# midi2neopixel.net
KiCad netlist of a schematic drawn in EAGLE
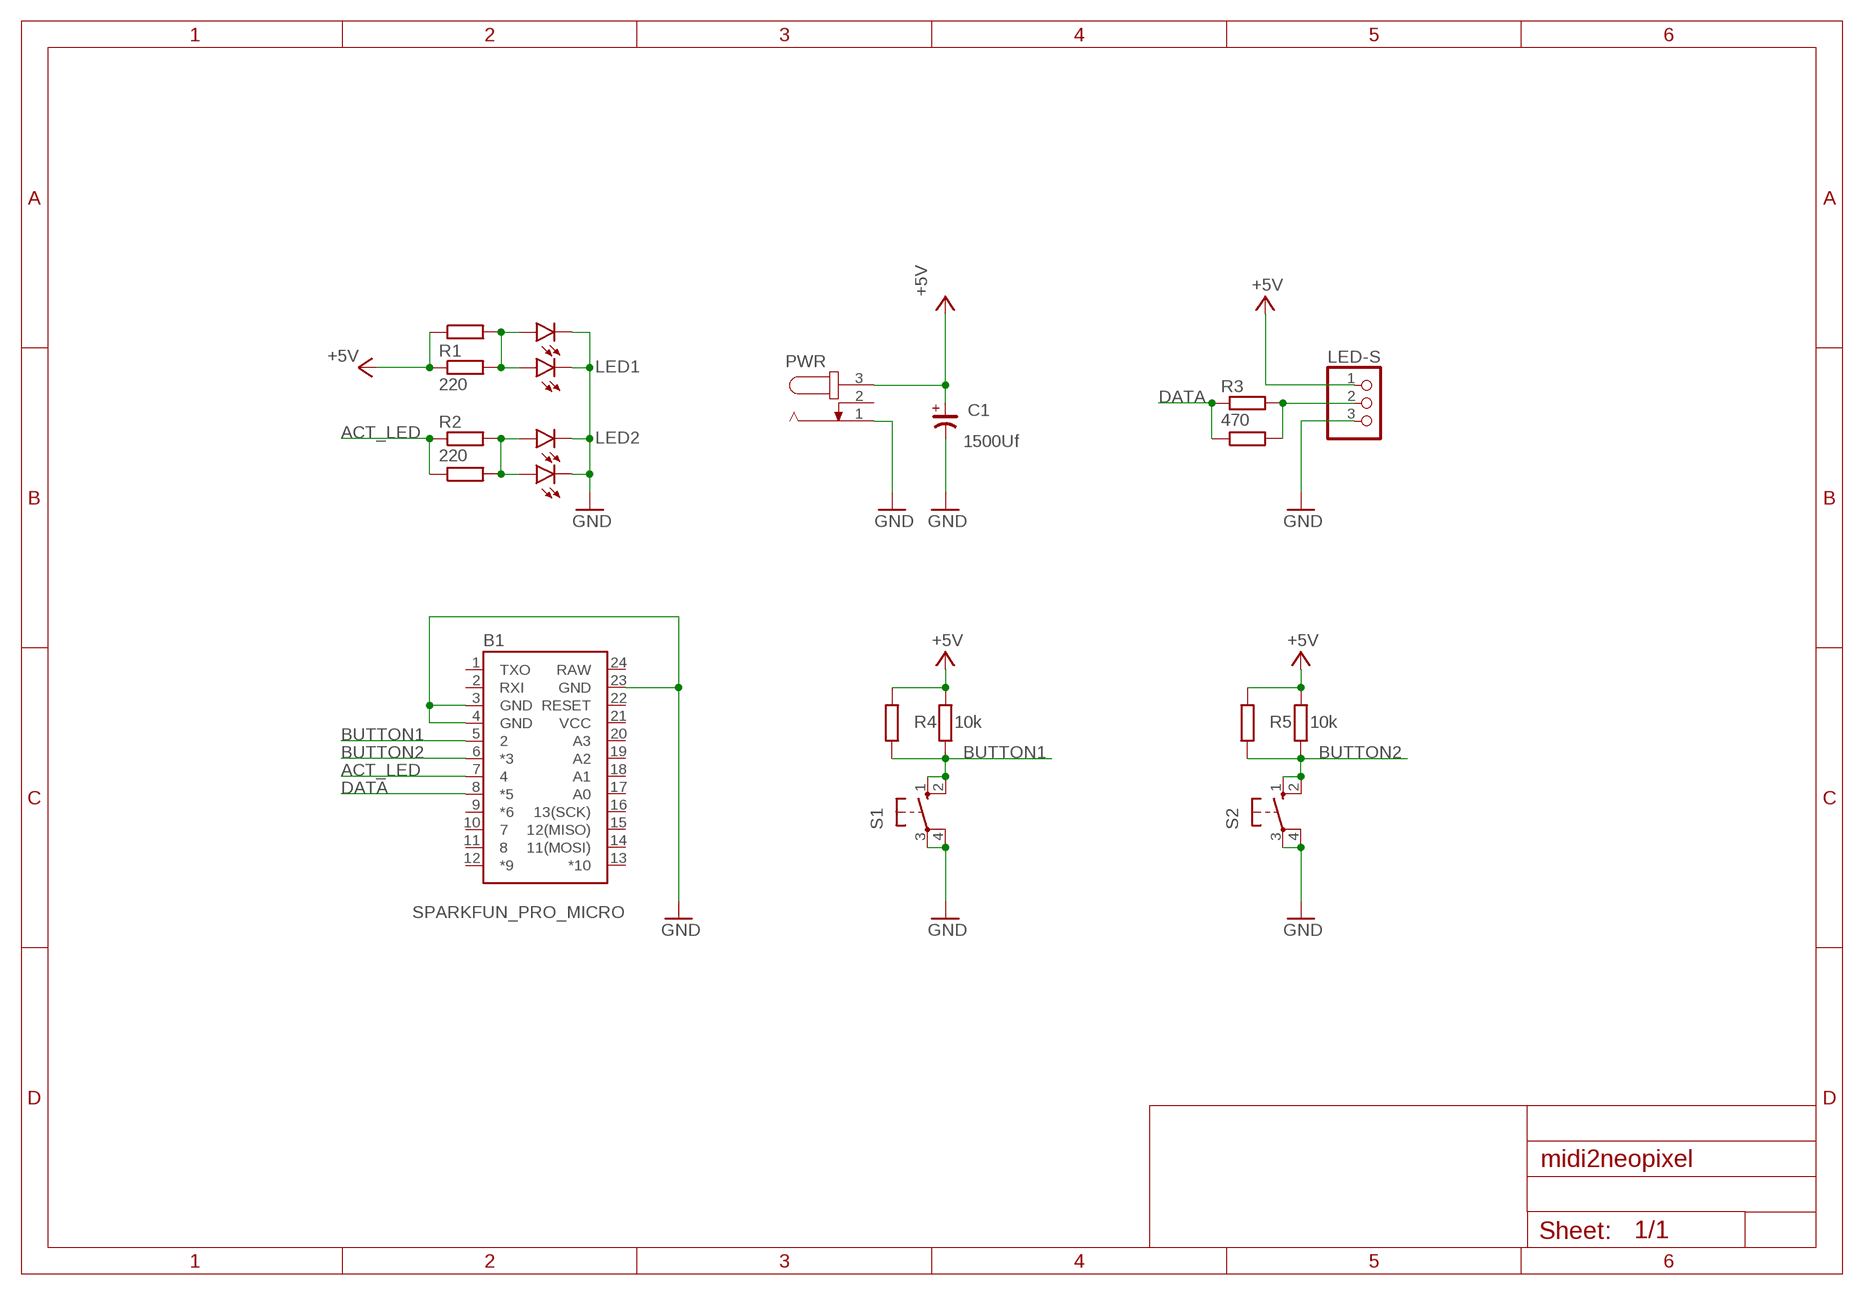
[diagram p0: schematic, sheet 1]

(export (version "E")
  (design (tool "Eeschema 10.0.6"))
  (components
    (comp (ref "B1")
      (value "SPARKFUN_PRO_MICRO")
      (footprint "eagle-import:SPARKFUN_PRO_MICRO")
      (libsource (lib "eagle-import") (part "SPARKFUN_PRO_MICRO"))
    )
    (comp (ref "C1")
      (value "1500Uf")
      (footprint "eagle-import:CEH-050-100X200")
      (libsource (lib "eagle-import") (part "CP_EH-050-100X200"))
    )
    (comp (ref "LED-S")
      (value "PINHD-1X3")
      (footprint "eagle-import:1X03")
      (libsource (lib "eagle-import") (part "PINHD-1X3"))
    )
    (comp (ref "LED1")
      (value "Green")
      (footprint "eagle-import:LED3MM")
      (libsource (lib "eagle-import") (part "LED3MM"))
    )
    (comp (ref "LED2")
      (value "Red")
      (footprint "eagle-import:LED3MM")
      (libsource (lib "eagle-import") (part "LED3MM"))
    )
    (comp (ref "LEDX1")
      (value "LEDSML0603")
      (footprint "eagle-import:SML0603")
      (libsource (lib "eagle-import") (part "LEDSML0603"))
    )
    (comp (ref "LEDX2")
      (value "LEDSML0603")
      (footprint "eagle-import:SML0603")
      (libsource (lib "eagle-import") (part "LEDSML0603"))
    )
    (comp (ref "PWR")
      (value "JACK-PLUG0")
      (footprint "eagle-import:SPC4077")
      (libsource (lib "eagle-import") (part "JACK-PLUG0"))
    )
    (comp (ref "R1")
      (value "220")
      (footprint "eagle-import:0207_7")
      (libsource (lib "eagle-import") (part "R-EU_0207/7"))
    )
    (comp (ref "R2")
      (value "220")
      (footprint "eagle-import:0207_7")
      (libsource (lib "eagle-import") (part "R-EU_0207/7"))
    )
    (comp (ref "R3")
      (value "470")
      (footprint "eagle-import:0207_7")
      (libsource (lib "eagle-import") (part "R-EU_0207/7"))
    )
    (comp (ref "R4")
      (value "10k")
      (footprint "eagle-import:0207_7")
      (libsource (lib "eagle-import") (part "R-EU_0207/7"))
    )
    (comp (ref "R5")
      (value "10k")
      (footprint "eagle-import:0207_7")
      (libsource (lib "eagle-import") (part "R-EU_0207/7"))
    )
    (comp (ref "RR1")
      (value "220")
      (footprint "eagle-import:R0603")
      (libsource (lib "eagle-import") (part "R-EU_R0603"))
    )
    (comp (ref "RR2")
      (value "220")
      (footprint "eagle-import:R0603")
      (libsource (lib "eagle-import") (part "R-EU_R0603"))
    )
    (comp (ref "RR3")
      (value "470")
      (footprint "eagle-import:R0603")
      (libsource (lib "eagle-import") (part "R-EU_R0603"))
    )
    (comp (ref "RR4")
      (value "10k")
      (footprint "eagle-import:R0603")
      (libsource (lib "eagle-import") (part "R-EU_R0603"))
    )
    (comp (ref "RR5")
      (value "10k")
      (footprint "eagle-import:R0603")
      (libsource (lib "eagle-import") (part "R-EU_R0603"))
    )
    (comp (ref "S1")
      (value "10-XX")
      (footprint "eagle-import:B3F-10XX")
      (fields (field (name "MPN") "B3F-1000"))
      (libsource (lib "eagle-import") (part "10-XX"))
    )
    (comp (ref "S2")
      (value "10-XX")
      (footprint "eagle-import:B3F-10XX")
      (fields (field (name "MPN") "B3F-1000"))
      (libsource (lib "eagle-import") (part "10-XX"))
    )
  )
  (nets
    (net (code "1") (name "+5V") (class "Default")
      (node (ref "C1") (pin "+") (pinfunction "+_+") (pintype "passive"))
      (node (ref "LED-S") (pin "1") (pinfunction "1_1") (pintype "passive"))
      (node (ref "PWR") (pin "3") (pinfunction "3_3") (pintype "passive"))
      (node (ref "R1") (pin "1") (pinfunction "1_1") (pintype "passive"))
      (node (ref "R4") (pin "2") (pinfunction "2_2") (pintype "passive"))
      (node (ref "R5") (pin "2") (pinfunction "2_2") (pintype "passive"))
      (node (ref "RR1") (pin "1") (pinfunction "1_1") (pintype "passive"))
      (node (ref "RR4") (pin "2") (pinfunction "2_2") (pintype "passive"))
      (node (ref "RR5") (pin "2") (pinfunction "2_2") (pintype "passive"))
    )
    (net (code "2") (name "/ACT_LED") (class "Default")
      (node (ref "B1") (pin "7") (pinfunction "4_7") (pintype "bidirectional"))
      (node (ref "R2") (pin "1") (pinfunction "1_1") (pintype "passive"))
      (node (ref "RR2") (pin "1") (pinfunction "1_1") (pintype "passive"))
    )
    (net (code "3") (name "/BUTTON1") (class "Default")
      (node (ref "B1") (pin "5") (pinfunction "2_5") (pintype "bidirectional"))
      (node (ref "R4") (pin "1") (pinfunction "1_1") (pintype "passive"))
      (node (ref "RR4") (pin "1") (pinfunction "1_1") (pintype "passive"))
      (node (ref "S1") (pin "1") (pinfunction "S_1") (pintype "passive"))
      (node (ref "S1") (pin "2") (pinfunction "S1_2") (pintype "passive"))
    )
    (net (code "4") (name "/BUTTON2") (class "Default")
      (node (ref "B1") (pin "6") (pinfunction "*3_6") (pintype "bidirectional"))
      (node (ref "R5") (pin "1") (pinfunction "1_1") (pintype "passive"))
      (node (ref "RR5") (pin "1") (pinfunction "1_1") (pintype "passive"))
      (node (ref "S2") (pin "1") (pinfunction "S_1") (pintype "passive"))
      (node (ref "S2") (pin "2") (pinfunction "S1_2") (pintype "passive"))
    )
    (net (code "5") (name "/DATA") (class "Default")
      (node (ref "B1") (pin "8") (pinfunction "*5_8") (pintype "bidirectional"))
      (node (ref "R3") (pin "1") (pinfunction "1_1") (pintype "passive"))
      (node (ref "RR3") (pin "1") (pinfunction "1_1") (pintype "passive"))
    )
    (net (code "6") (name "/RAW") (class "Default")
      (node (ref "B1") (pin "24") (pinfunction "RAW_24") (pintype "power_in"))
    )
    (net (code "7") (name "/VCC") (class "Default")
      (node (ref "B1") (pin "21") (pinfunction "VCC_21") (pintype "power_in"))
    )
    (net (code "8") (name "GND") (class "Default")
      (node (ref "B1") (pin "23") (pinfunction "GND_23") (pintype "power_in"))
      (node (ref "B1") (pin "3") (pinfunction "GND_3") (pintype "power_in"))
      (node (ref "B1") (pin "4") (pinfunction "GND_4") (pintype "power_in"))
      (node (ref "C1") (pin "-") (pinfunction "-_-") (pintype "passive"))
      (node (ref "LED-S") (pin "3") (pinfunction "3_3") (pintype "passive"))
      (node (ref "LED1") (pin "K") (pinfunction "C_K") (pintype "passive"))
      (node (ref "LED2") (pin "K") (pinfunction "C_K") (pintype "passive"))
      (node (ref "LEDX1") (pin "C") (pinfunction "C_C") (pintype "passive"))
      (node (ref "LEDX2") (pin "C") (pinfunction "C_C") (pintype "passive"))
      (node (ref "PWR") (pin "1") (pinfunction "1_1") (pintype "passive"))
      (node (ref "S1") (pin "3") (pinfunction "P_3") (pintype "passive"))
      (node (ref "S1") (pin "4") (pinfunction "P1_4") (pintype "passive"))
      (node (ref "S2") (pin "3") (pinfunction "P_3") (pintype "passive"))
      (node (ref "S2") (pin "4") (pinfunction "P1_4") (pintype "passive"))
    )
    (net (code "9") (name "Net-(LED-S-Pad2)") (class "Default")
      (node (ref "LED-S") (pin "2") (pinfunction "2_2") (pintype "passive"))
      (node (ref "R3") (pin "2") (pinfunction "2_2") (pintype "passive"))
      (node (ref "RR3") (pin "2") (pinfunction "2_2") (pintype "passive"))
    )
    (net (code "10") (name "Net-(LED1-PadA)") (class "Default")
      (node (ref "LED1") (pin "A") (pinfunction "A_A") (pintype "passive"))
      (node (ref "LEDX1") (pin "A") (pinfunction "A_A") (pintype "passive"))
      (node (ref "R1") (pin "2") (pinfunction "2_2") (pintype "passive"))
      (node (ref "RR1") (pin "2") (pinfunction "2_2") (pintype "passive"))
    )
    (net (code "11") (name "Net-(LED2-PadA)") (class "Default")
      (node (ref "LED2") (pin "A") (pinfunction "A_A") (pintype "passive"))
      (node (ref "LEDX2") (pin "A") (pinfunction "A_A") (pintype "passive"))
      (node (ref "R2") (pin "2") (pinfunction "2_2") (pintype "passive"))
      (node (ref "RR2") (pin "2") (pinfunction "2_2") (pintype "passive"))
    )
    (net (code "12") (name "unconnected-(B1-*6-Pad9)") (class "Default")
      (node (ref "B1") (pin "9") (pinfunction "*6_9") (pintype "bidirectional"))
    )
    (net (code "13") (name "unconnected-(B1-*9-Pad12)") (class "Default")
      (node (ref "B1") (pin "12") (pinfunction "*9_12") (pintype "bidirectional"))
    )
    (net (code "14") (name "unconnected-(B1-*10-Pad13)") (class "Default")
      (node (ref "B1") (pin "13") (pinfunction "*10_13") (pintype "bidirectional"))
    )
    (net (code "15") (name "unconnected-(B1-7-Pad10)") (class "Default")
      (node (ref "B1") (pin "10") (pinfunction "7_10") (pintype "bidirectional"))
    )
    (net (code "16") (name "unconnected-(B1-8-Pad11)") (class "Default")
      (node (ref "B1") (pin "11") (pinfunction "8_11") (pintype "bidirectional"))
    )
    (net (code "17") (name "unconnected-(B1-11(MOSI)-Pad14)") (class "Default")
      (node (ref "B1") (pin "14") (pinfunction "11(MOSI)_14") (pintype "bidirectional"))
    )
    (net (code "18") (name "unconnected-(B1-12(MISO)-Pad15)") (class "Default")
      (node (ref "B1") (pin "15") (pinfunction "12(MISO)_15") (pintype "bidirectional"))
    )
    (net (code "19") (name "unconnected-(B1-13(SCK)-Pad16)") (class "Default")
      (node (ref "B1") (pin "16") (pinfunction "13(SCK)_16") (pintype "bidirectional"))
    )
    (net (code "20") (name "unconnected-(B1-A0-Pad17)") (class "Default")
      (node (ref "B1") (pin "17") (pinfunction "A0_17") (pintype "bidirectional"))
    )
    (net (code "21") (name "unconnected-(B1-A1-Pad18)") (class "Default")
      (node (ref "B1") (pin "18") (pinfunction "A1_18") (pintype "bidirectional"))
    )
    (net (code "22") (name "unconnected-(B1-A2-Pad19)") (class "Default")
      (node (ref "B1") (pin "19") (pinfunction "A2_19") (pintype "bidirectional"))
    )
    (net (code "23") (name "unconnected-(B1-A3-Pad20)") (class "Default")
      (node (ref "B1") (pin "20") (pinfunction "A3_20") (pintype "bidirectional"))
    )
    (net (code "24") (name "unconnected-(B1-RESET-Pad22)") (class "Default")
      (node (ref "B1") (pin "22") (pinfunction "RESET_22") (pintype "bidirectional"))
    )
    (net (code "25") (name "unconnected-(B1-RXI-Pad2)") (class "Default")
      (node (ref "B1") (pin "2") (pinfunction "RXI_2") (pintype "bidirectional"))
    )
    (net (code "26") (name "unconnected-(B1-TXO-Pad1)") (class "Default")
      (node (ref "B1") (pin "1") (pinfunction "TXO_1") (pintype "bidirectional"))
    )
    (net (code "27") (name "unconnected-(PWR-Pad2)") (class "Default")
      (node (ref "PWR") (pin "2") (pinfunction "2_2") (pintype "passive"))
    )
  )
)
